# FETs.net
KiCad netlist of a schematic drawn in Altium Designer
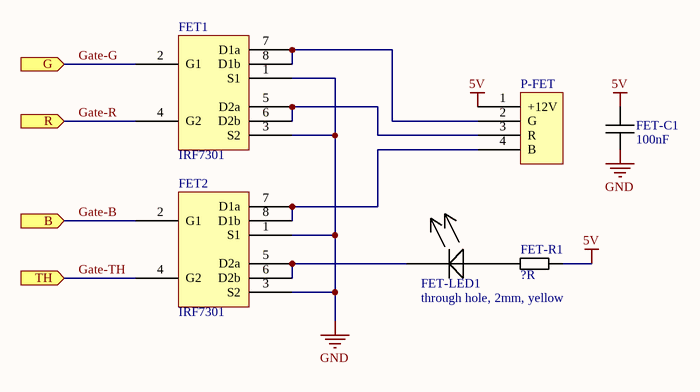
[diagram p0: FETs.SchDoc]

(export (version "E")
  (design (tool "Eeschema 10.0.6"))
  (components
    (comp (ref "FET-C1")
      (value "100nF")
      (footprint "C 0805 / 2012")
      (libsource (lib "Standard") (part "Capacitor"))
    )
    (comp (ref "FET-LED1")
      (value "through hole, 2mm, yellow")
      (footprint "LED 3mm")
      (libsource (lib "LEDs") (part "LED"))
    )
    (comp (ref "FET-R1")
      (value "?R")
      (footprint "R 0805 / 2012")
      (libsource (lib "Standard") (part "Resistor"))
    )
    (comp (ref "FET1")
      (value "IRF7301")
      (footprint "SOIC-8")
      (libsource (lib "Core51822-related") (part "IRF7301"))
    )
    (comp (ref "FET2")
      (value "IRF7301")
      (footprint "SOIC-8")
      (libsource (lib "Core51822-related") (part "IRF7301"))
    )
    (comp (ref "P-FET")
      (value "LED strip RGB")
      (footprint "LED strip RGB connector")
      (libsource (lib "Core51822-related") (part "LED strip RGB"))
    )
  )
  (nets
    (net (code "1") (name "/Gate-B") (class "Default")
      (node (ref "FET2") (pin "2") (pinfunction "G1_2") (pintype "passive"))
    )
    (net (code "2") (name "/Gate-G") (class "Default")
      (node (ref "FET1") (pin "2") (pinfunction "G1_2") (pintype "passive"))
    )
    (net (code "3") (name "/Gate-R") (class "Default")
      (node (ref "FET1") (pin "4") (pinfunction "G2_4") (pintype "passive"))
    )
    (net (code "4") (name "/Gate-TH") (class "Default")
      (node (ref "FET2") (pin "4") (pinfunction "G2_4") (pintype "passive"))
    )
    (net (code "5") (name "5V") (class "Default")
      (node (ref "FET-C1") (pin "1") (pinfunction "1_1") (pintype "passive"))
      (node (ref "FET-R1") (pin "2") (pinfunction "2_2") (pintype "passive"))
      (node (ref "P-FET") (pin "1") (pinfunction "+12V_1") (pintype "passive"))
    )
    (net (code "6") (name "GND") (class "Default")
      (node (ref "FET-C1") (pin "2") (pinfunction "1_2") (pintype "passive"))
      (node (ref "FET1") (pin "1") (pinfunction "S1_1") (pintype "passive"))
      (node (ref "FET1") (pin "3") (pinfunction "S2_3") (pintype "passive"))
      (node (ref "FET2") (pin "1") (pinfunction "S1_1") (pintype "passive"))
      (node (ref "FET2") (pin "3") (pinfunction "S2_3") (pintype "passive"))
    )
    (net (code "7") (name "Net-(FET-LED1-+)") (class "Default")
      (node (ref "FET-LED1") (pin "1") (pinfunction "+_1") (pintype "passive"))
      (node (ref "FET-R1") (pin "1") (pinfunction "1_1") (pintype "passive"))
    )
    (net (code "8") (name "Net-(FET-LED1--)") (class "Default")
      (node (ref "FET-LED1") (pin "2") (pinfunction "-_2") (pintype "passive"))
      (node (ref "FET2") (pin "5") (pinfunction "D2a_5") (pintype "passive"))
      (node (ref "FET2") (pin "6") (pinfunction "D2b_6") (pintype "passive"))
    )
    (net (code "9") (name "Net-(FET1-D1a)") (class "Default")
      (node (ref "FET1") (pin "7") (pinfunction "D1a_7") (pintype "passive"))
      (node (ref "FET1") (pin "8") (pinfunction "D1b_8") (pintype "passive"))
      (node (ref "P-FET") (pin "2") (pinfunction "G_2") (pintype "passive"))
    )
    (net (code "10") (name "Net-(FET1-D2a)") (class "Default")
      (node (ref "FET1") (pin "5") (pinfunction "D2a_5") (pintype "passive"))
      (node (ref "FET1") (pin "6") (pinfunction "D2b_6") (pintype "passive"))
      (node (ref "P-FET") (pin "3") (pinfunction "R_3") (pintype "passive"))
    )
    (net (code "11") (name "Net-(FET2-D1a)") (class "Default")
      (node (ref "FET2") (pin "7") (pinfunction "D1a_7") (pintype "passive"))
      (node (ref "FET2") (pin "8") (pinfunction "D1b_8") (pintype "passive"))
      (node (ref "P-FET") (pin "4") (pinfunction "B_4") (pintype "passive"))
    )
  )
)
